# MCU.net
KiCad netlist of a schematic drawn in Altium Designer
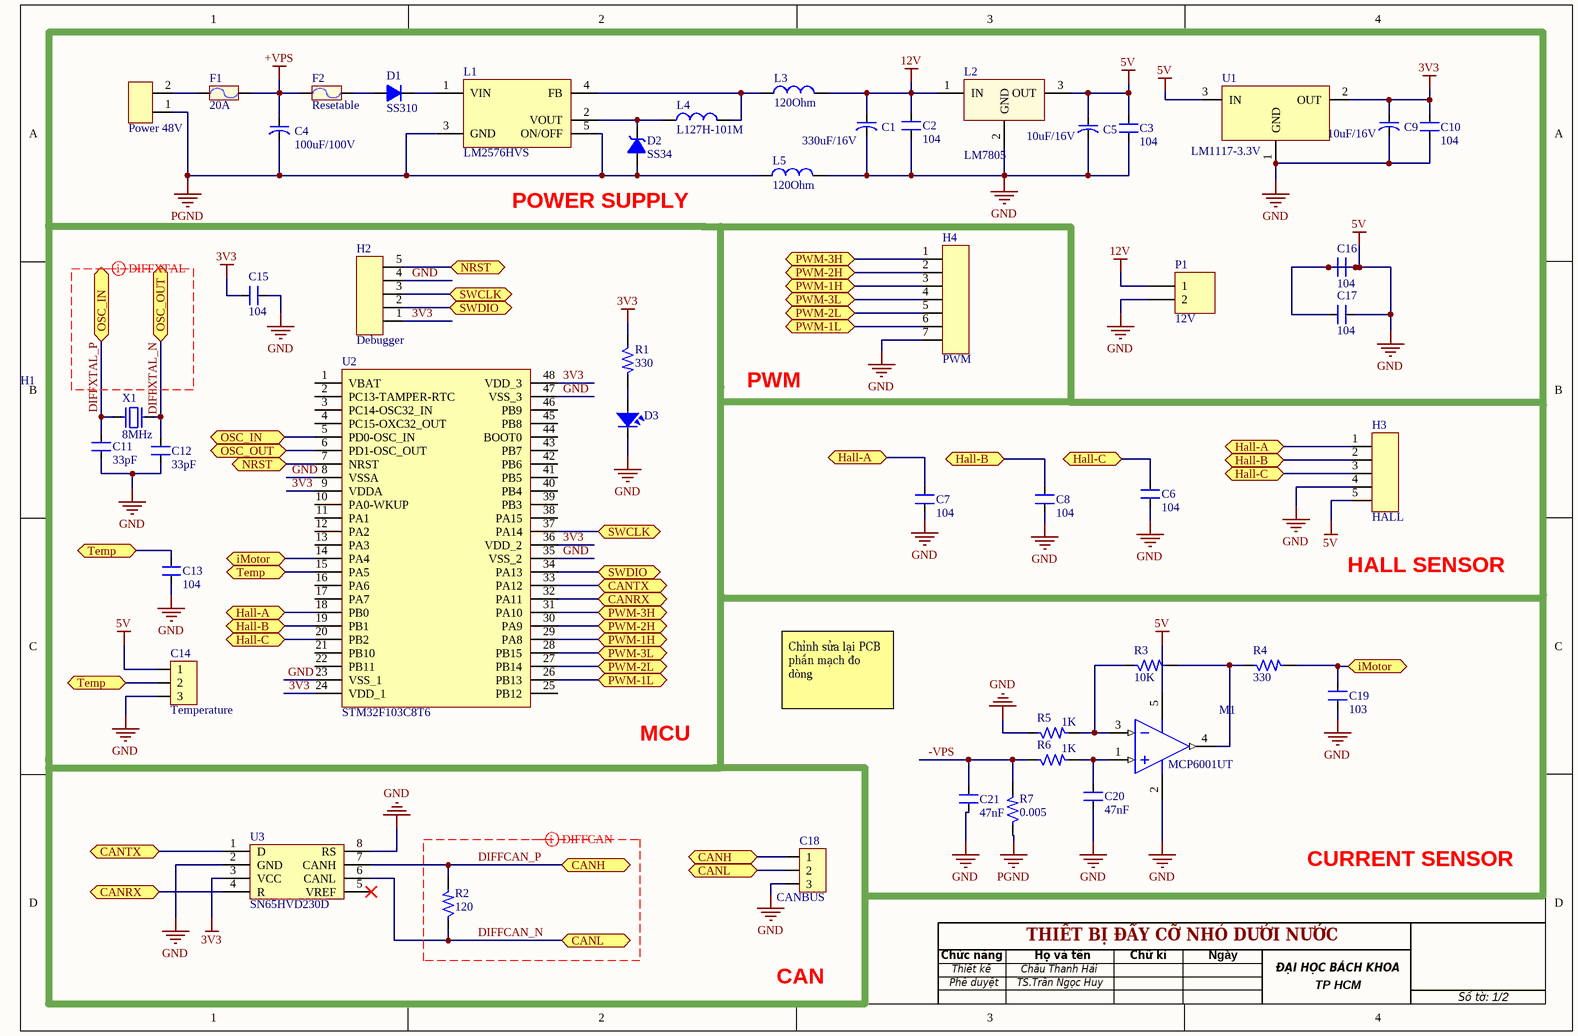
[diagram p0: MCU.SchDoc]

(export (version "E")
  (design (tool "Eeschema 10.0.6"))
  (components
    (comp (ref "C1")
      (value "330uF/16V")
      (footprint "330uF/16V")
      (libsource (lib "BLDC_Libraries") (part "330uF/16V"))
    )
    (comp (ref "C2")
      (value "104")
      (footprint "Non-Capacitor 104 SMD")
      (libsource (lib "BLDC_Libraries") (part "104"))
    )
    (comp (ref "C3")
      (value "104")
      (footprint "Non-Capacitor 104 SMD")
      (libsource (lib "BLDC_Libraries") (part "104"))
    )
    (comp (ref "C4")
      (value "100uF/100V")
      (footprint "100uF/100V")
      (description "DIP Footprint")
      (libsource (lib "BLDC_Libraries") (part "Polary Capacitor"))
    )
    (comp (ref "C5")
      (value "10uF/16V")
      (footprint "10uF/16V")
      (libsource (lib "BLDC_Libraries") (part "10uF/16V"))
    )
    (comp (ref "C6")
      (value "104")
      (footprint "Non-Capacitor 104 SMD")
      (libsource (lib "BLDC_Libraries") (part "104"))
    )
    (comp (ref "C7")
      (value "104")
      (footprint "Non-Capacitor 104 SMD")
      (libsource (lib "BLDC_Libraries") (part "104"))
    )
    (comp (ref "C8")
      (value "104")
      (footprint "Non-Capacitor 104 SMD")
      (libsource (lib "BLDC_Libraries") (part "104"))
    )
    (comp (ref "C9")
      (value "10uF/16V")
      (footprint "10uF/16V")
      (libsource (lib "BLDC_Libraries") (part "10uF/16V"))
    )
    (comp (ref "C10")
      (value "104")
      (footprint "Non-Capacitor 104 SMD")
      (libsource (lib "BLDC_Libraries") (part "104"))
    )
    (comp (ref "C11")
      (value "33pF")
      (footprint "Non-Capacitor 104 SMD")
      (libsource (lib "BLDC_Libraries") (part "104"))
    )
    (comp (ref "C12")
      (value "33pF")
      (footprint "Non-Capacitor 104 SMD")
      (libsource (lib "BLDC_Libraries") (part "104"))
    )
    (comp (ref "C13")
      (value "104")
      (footprint "Non-Capacitor 104 SMD")
      (libsource (lib "BLDC_Libraries") (part "104"))
    )
    (comp (ref "C14")
      (value "Temperature")
      (footprint "Header3")
      (description "Header IDC, 3 x 1 Pin Vertical 2.54mm Pitch (Non-Boxed, Male)")
      (fields
        (field (name "MANUFACTURER") "Würth Elektronik eiSos GmbH")
        (field (name "PARTNO") "613002143121")
        (field (name "CREATED BY") "Karrer Zheng")
      )
      (libsource (lib "LIBRARY") (part "Header3"))
    )
    (comp (ref "C15")
      (value "104")
      (footprint "Non-Capacitor 104 SMD")
      (libsource (lib "BLDC_Libraries") (part "104"))
    )
    (comp (ref "C16")
      (value "104")
      (footprint "Non-Capacitor 104 SMD")
      (libsource (lib "BLDC_Libraries") (part "104"))
    )
    (comp (ref "C17")
      (value "104")
      (footprint "Non-Capacitor 104 SMD")
      (libsource (lib "BLDC_Libraries") (part "104"))
    )
    (comp (ref "C18")
      (value "CANBUS")
      (footprint "Header3")
      (description "Header IDC, 3 x 1 Pin Vertical 2.54mm Pitch (Non-Boxed, Male)")
      (fields
        (field (name "MANUFACTURER") "Würth Elektronik eiSos GmbH")
        (field (name "PARTNO") "613002143121")
        (field (name "CREATED BY") "Karrer Zheng")
      )
      (libsource (lib "LIBRARY") (part "Header3"))
    )
    (comp (ref "C19")
      (value "103")
      (footprint "Non-Capacitor 104 SMD")
      (libsource (lib "BLDC_Libraries") (part "104"))
    )
    (comp (ref "C20")
      (value "47nF")
      (footprint "Non-Capacitor 104 SMD")
      (libsource (lib "BLDC_Libraries") (part "104"))
    )
    (comp (ref "C21")
      (value "47nF")
      (footprint "Non-Capacitor 104 SMD")
      (libsource (lib "BLDC_Libraries") (part "104"))
    )
    (comp (ref "D1") (value "SS310") (footprint "SS310") (libsource (lib "BLDC_Libraries") (part "SS310")))
    (comp (ref "D2") (value "SS34") (footprint "SS34") (libsource (lib "BLDC_Libraries") (part "SS34")))
    (comp (ref "D3")
      (value "LED SMD0603")
      (footprint "Led SMD0603")
      (libsource (lib "BLDC_Libraries") (part "LED SMD0603"))
    )
    (comp (ref "F1") (value "20A") (footprint "Fuse 20A") (libsource (lib "BLDC_Libraries") (part "Fuse")))
    (comp (ref "F2")
      (value "Resetable")
      (footprint "PTC Resettable Fuses")
      (libsource (lib "BLDC_Libraries") (part "Fuse"))
    )
    (comp (ref "H1")
      (value "Power 48V")
      (footprint "Header 2")
      (libsource (lib "BLDC_Libraries") (part "Header 2x1"))
    )
    (comp (ref "H2")
      (value "Debugger")
      (footprint "Header 5")
      (libsource (lib "BLDC_Libraries") (part "Header 5x1"))
    )
    (comp (ref "H3") (value "HALL") (footprint "Header_5_B") (libsource (lib "") (part "Header 5x1_1")))
    (comp (ref "H4")
      (value "PWM")
      (footprint "Header 7 Male")
      (libsource (lib "BLDC_Libraries") (part "Header 7x1"))
    )
    (comp (ref "L1")
      (value "LM2576HVS")
      (footprint "LM2576 SMD")
      (libsource (lib "BLDC_Libraries") (part "LM2576HVS"))
    )
    (comp (ref "L2")
      (value "LM7805")
      (footprint "LM7805 SMD")
      (libsource (lib "BLDC_Libraries") (part "LM7805"))
    )
    (comp (ref "L3")
      (value "120Ohm")
      (footprint "Ferrite Beads")
      (libsource (lib "BLDC_Libraries") (part "Ferrite Beads"))
    )
    (comp (ref "L4")
      (value "L127H-101M")
      (footprint "L127H-101M")
      (libsource (lib "BLDC_Libraries") (part "L127H-101M"))
    )
    (comp (ref "L5")
      (value "120Ohm")
      (footprint "Ferrite Beads")
      (libsource (lib "BLDC_Libraries") (part "Ferrite Beads"))
    )
    (comp (ref "M1")
      (value "MCP6001UT")
      (footprint "MCP6001UT")
      (libsource (lib "BLDC_Libraries") (part "MCP6001UT"))
    )
    (comp (ref "P1")
      (value "12V")
      (footprint "HDR1X2")
      (description "Header, 2-Pin")
      (fields (field (name "PUBLISHER") "Altium Limited"))
      (libsource (lib "NBBLib 14-03-2012") (part "Header 2"))
    )
    (comp (ref "R1")
      (value "330")
      (footprint "Resistor SMD 0603")
      (libsource (lib "BLDC_Libraries") (part "Resistors"))
    )
    (comp (ref "R2")
      (value "120")
      (footprint "Resistor SMD 0603")
      (libsource (lib "BLDC_Libraries") (part "Resistors"))
    )
    (comp (ref "R3")
      (value "10K")
      (footprint "Resistor SMD 0603")
      (libsource (lib "BLDC_Libraries") (part "Resistors"))
    )
    (comp (ref "R4")
      (value "330")
      (footprint "Resistor SMD 0603")
      (libsource (lib "BLDC_Libraries") (part "Resistors"))
    )
    (comp (ref "R5")
      (value "1K")
      (footprint "Resistor SMD 0603")
      (libsource (lib "BLDC_Libraries") (part "Resistors"))
    )
    (comp (ref "R6")
      (value "1K")
      (footprint "Resistor SMD 0603")
      (libsource (lib "BLDC_Libraries") (part "Resistors"))
    )
    (comp (ref "R7")
      (value "0.005")
      (footprint "Shunt")
      (libsource (lib "BLDC_Libraries") (part "Shunt Resistor"))
    )
    (comp (ref "U1")
      (value "LM1117-3.3V")
      (footprint "SOT223")
      (description "800mA Low-Dropout Linear Regulator")
      (fields (field (name "CREATOR") "Nguyen Ba Bien"))
      (libsource (lib "LIBRARY") (part "LM1117"))
    )
    (comp (ref "U2")
      (value "STM32F103C8T6")
      (footprint "STM32F103C8T6")
      (description "ARM® 32-bit Cortex®-M3")
      (libsource (lib "BLDC_Libraries") (part "STM32F103C8T6"))
    )
    (comp (ref "U3")
      (value "SN65HVD230D")
      (footprint "SN65HVD230D")
      (libsource (lib "BLDC_Libraries") (part "SN65HVD230D"))
    )
    (comp (ref "X1") (value "8MHz") (footprint "Crystal") (libsource (lib "BLDC_Libraries") (part "Crystal")))
  )
  (nets
    (net (code "1") (name "+VPS") (class "Default")
      (node (ref "C4") (pin "1") (pinfunction "1_1") (pintype "passive"))
      (node (ref "F1") (pin "2") (pinfunction "2_2") (pintype "passive"))
      (node (ref "F2") (pin "1") (pinfunction "1_1") (pintype "passive"))
    )
    (net (code "2") (name "/-VPS") (class "Default")
      (node (ref "C21") (pin "2") (pinfunction "2_2") (pintype "passive"))
      (node (ref "R6") (pin "1") (pinfunction "1_1") (pintype "passive"))
      (node (ref "R7") (pin "2") (pinfunction "2_2") (pintype "passive"))
    )
    (net (code "3") (name "/CANRX") (class "Default")
      (node (ref "U2") (pin "32") (pinfunction "PA11_32") (pintype "passive"))
      (node (ref "U3") (pin "4") (pinfunction "R_4") (pintype "passive"))
    )
    (net (code "4") (name "/CANTX") (class "Default")
      (node (ref "U2") (pin "33") (pinfunction "PA12_33") (pintype "passive"))
      (node (ref "U3") (pin "1") (pinfunction "D_1") (pintype "passive"))
    )
    (net (code "5") (name "/DIFFCAN_N") (class "Default")
      (node (ref "C18") (pin "2") (pinfunction "2_2") (pintype "passive"))
      (node (ref "R2") (pin "1") (pinfunction "1_1") (pintype "passive"))
      (node (ref "U3") (pin "6") (pinfunction "CANL_6") (pintype "passive"))
    )
    (net (code "6") (name "/DIFFCAN_P") (class "Default")
      (node (ref "C18") (pin "1") (pinfunction "1_1") (pintype "passive"))
      (node (ref "R2") (pin "2") (pinfunction "2_2") (pintype "passive"))
      (node (ref "U3") (pin "7") (pinfunction "CANH_7") (pintype "passive"))
    )
    (net (code "7") (name "/DIFFXTAL_N") (class "Default")
      (node (ref "C12") (pin "2") (pinfunction "2_2") (pintype "passive"))
      (node (ref "U2") (pin "6") (pinfunction "PD1-OSC_OUT_6") (pintype "passive"))
      (node (ref "X1") (pin "2") (pinfunction "2_2") (pintype "passive"))
    )
    (net (code "8") (name "/DIFFXTAL_P") (class "Default")
      (node (ref "C11") (pin "2") (pinfunction "2_2") (pintype "passive"))
      (node (ref "U2") (pin "5") (pinfunction "PD0-OSC_IN_5") (pintype "passive"))
      (node (ref "X1") (pin "1") (pinfunction "1_1") (pintype "passive"))
    )
    (net (code "9") (name "/Hall-A") (class "Default")
      (node (ref "C7") (pin "2") (pinfunction "2_2") (pintype "passive"))
      (node (ref "H3") (pin "1") (pinfunction "1_1") (pintype "passive"))
      (node (ref "U2") (pin "18") (pinfunction "PB0_18") (pintype "passive"))
    )
    (net (code "10") (name "/Hall-B") (class "Default")
      (node (ref "C8") (pin "2") (pinfunction "2_2") (pintype "passive"))
      (node (ref "H3") (pin "2") (pinfunction "2_2") (pintype "passive"))
      (node (ref "U2") (pin "19") (pinfunction "PB1_19") (pintype "passive"))
    )
    (net (code "11") (name "/Hall-C") (class "Default")
      (node (ref "C6") (pin "2") (pinfunction "2_2") (pintype "passive"))
      (node (ref "H3") (pin "3") (pinfunction "3_3") (pintype "passive"))
      (node (ref "U2") (pin "20") (pinfunction "PB2_20") (pintype "passive"))
    )
    (net (code "12") (name "/NRST") (class "Default")
      (node (ref "H2") (pin "5") (pinfunction "5_5") (pintype "passive"))
      (node (ref "U2") (pin "7") (pinfunction "NRST_7") (pintype "passive"))
    )
    (net (code "13") (name "/PWM-1H") (class "Default")
      (node (ref "H4") (pin "3") (pinfunction "3_3") (pintype "passive"))
      (node (ref "U2") (pin "29") (pinfunction "PA8_29") (pintype "passive"))
    )
    (net (code "14") (name "/PWM-1L") (class "Default")
      (node (ref "H4") (pin "6") (pinfunction "6_6") (pintype "passive"))
      (node (ref "U2") (pin "26") (pinfunction "PB13_26") (pintype "passive"))
    )
    (net (code "15") (name "/PWM-2H") (class "Default")
      (node (ref "H4") (pin "2") (pinfunction "2_2") (pintype "passive"))
      (node (ref "U2") (pin "30") (pinfunction "PA9_30") (pintype "passive"))
    )
    (net (code "16") (name "/PWM-2L") (class "Default")
      (node (ref "H4") (pin "5") (pinfunction "5_5") (pintype "passive"))
      (node (ref "U2") (pin "27") (pinfunction "PB14_27") (pintype "passive"))
    )
    (net (code "17") (name "/PWM-3H") (class "Default")
      (node (ref "H4") (pin "1") (pinfunction "1_1") (pintype "passive"))
      (node (ref "U2") (pin "31") (pinfunction "PA10_31") (pintype "passive"))
    )
    (net (code "18") (name "/PWM-3L") (class "Default")
      (node (ref "H4") (pin "4") (pinfunction "4_4") (pintype "passive"))
      (node (ref "U2") (pin "28") (pinfunction "PB15_28") (pintype "passive"))
    )
    (net (code "19") (name "/SWCLK") (class "Default")
      (node (ref "H2") (pin "3") (pinfunction "3_3") (pintype "passive"))
      (node (ref "U2") (pin "37") (pinfunction "PA14_37") (pintype "passive"))
    )
    (net (code "20") (name "/SWDIO") (class "Default")
      (node (ref "H2") (pin "2") (pinfunction "2_2") (pintype "passive"))
      (node (ref "U2") (pin "34") (pinfunction "PA13_34") (pintype "passive"))
    )
    (net (code "21") (name "/Temp") (class "Default")
      (node (ref "C13") (pin "1") (pinfunction "1_1") (pintype "passive"))
      (node (ref "C14") (pin "2") (pinfunction "2_2") (pintype "passive"))
      (node (ref "U2") (pin "15") (pinfunction "PA5_15") (pintype "passive"))
    )
    (net (code "22") (name "/iMotor") (class "Default")
      (node (ref "C19") (pin "2") (pinfunction "2_2") (pintype "passive"))
      (node (ref "R4") (pin "2") (pinfunction "2_2") (pintype "passive"))
      (node (ref "U2") (pin "14") (pinfunction "PA4_14") (pintype "passive"))
    )
    (net (code "23") (name "3V3") (class "Default")
      (node (ref "C10") (pin "2") (pinfunction "2_2") (pintype "passive"))
      (node (ref "C15") (pin "2") (pinfunction "2_2") (pintype "passive"))
      (node (ref "C9") (pin "1") (pinfunction "1_1") (pintype "passive"))
      (node (ref "H2") (pin "1") (pinfunction "1_1") (pintype "passive"))
      (node (ref "R1") (pin "1") (pinfunction "1_1") (pintype "passive"))
      (node (ref "U1") (pin "2") (pinfunction "OUT_2") (pintype "passive"))
      (node (ref "U2") (pin "24") (pinfunction "VDD_1_24") (pintype "passive"))
      (node (ref "U2") (pin "36") (pinfunction "VDD_2_36") (pintype "passive"))
      (node (ref "U2") (pin "48") (pinfunction "VDD_3_48") (pintype "passive"))
      (node (ref "U2") (pin "9") (pinfunction "VDDA_9") (pintype "passive"))
      (node (ref "U3") (pin "3") (pinfunction "VCC_3") (pintype "passive"))
    )
    (net (code "24") (name "5V") (class "Default")
      (node (ref "C1") (pin "2") (pinfunction "2_2") (pintype "passive"))
      (node (ref "C10") (pin "1") (pinfunction "1_1") (pintype "passive"))
      (node (ref "C11") (pin "1") (pinfunction "1_1") (pintype "passive"))
      (node (ref "C12") (pin "1") (pinfunction "1_1") (pintype "passive"))
      (node (ref "C13") (pin "2") (pinfunction "2_2") (pintype "passive"))
      (node (ref "C14") (pin "1") (pinfunction "1_1") (pintype "passive"))
      (node (ref "C14") (pin "3") (pinfunction "3_3") (pintype "passive"))
      (node (ref "C15") (pin "1") (pinfunction "1_1") (pintype "passive"))
      (node (ref "C16") (pin "1") (pinfunction "1_1") (pintype "passive"))
      (node (ref "C16") (pin "2") (pinfunction "2_2") (pintype "passive"))
      (node (ref "C17") (pin "1") (pinfunction "1_1") (pintype "passive"))
      (node (ref "C17") (pin "2") (pinfunction "2_2") (pintype "passive"))
      (node (ref "C18") (pin "3") (pinfunction "3_3") (pintype "passive"))
      (node (ref "C19") (pin "1") (pinfunction "1_1") (pintype "passive"))
      (node (ref "C2") (pin "1") (pinfunction "1_1") (pintype "passive"))
      (node (ref "C20") (pin "1") (pinfunction "1_1") (pintype "passive"))
      (node (ref "C21") (pin "1") (pinfunction "1_1") (pintype "passive"))
      (node (ref "C3") (pin "1") (pinfunction "1_1") (pintype "passive"))
      (node (ref "C3") (pin "2") (pinfunction "2_2") (pintype "passive"))
      (node (ref "C5") (pin "1") (pinfunction "1_1") (pintype "passive"))
      (node (ref "C5") (pin "2") (pinfunction "2_2") (pintype "passive"))
      (node (ref "C6") (pin "1") (pinfunction "1_1") (pintype "passive"))
      (node (ref "C7") (pin "1") (pinfunction "1_1") (pintype "passive"))
      (node (ref "C8") (pin "1") (pinfunction "1_1") (pintype "passive"))
      (node (ref "C9") (pin "2") (pinfunction "2_2") (pintype "passive"))
      (node (ref "D3") (pin "2") (pinfunction "2_2") (pintype "passive"))
      (node (ref "H2") (pin "4") (pinfunction "4_4") (pintype "passive"))
      (node (ref "H3") (pin "4") (pinfunction "4_4") (pintype "passive"))
      (node (ref "H3") (pin "5") (pinfunction "5_5") (pintype "passive"))
      (node (ref "H4") (pin "7") (pinfunction "7_7") (pintype "passive"))
      (node (ref "L2") (pin "2") (pinfunction "GND_2") (pintype "passive"))
      (node (ref "L2") (pin "3") (pinfunction "OUT_3") (pintype "passive"))
      (node (ref "L5") (pin "2") (pinfunction "2_2") (pintype "passive"))
      (node (ref "M1") (pin "2") (pinfunction "V-_2") (pintype "power_in"))
      (node (ref "M1") (pin "5") (pinfunction "V+_5") (pintype "power_in"))
      (node (ref "P1") (pin "2") (pinfunction "2_2") (pintype "passive"))
      (node (ref "R5") (pin "1") (pinfunction "1_1") (pintype "passive"))
      (node (ref "U1") (pin "1") (pinfunction "GND_1") (pintype "passive"))
      (node (ref "U1") (pin "3") (pinfunction "IN_3") (pintype "passive"))
      (node (ref "U2") (pin "23") (pinfunction "VSS_1_23") (pintype "passive"))
      (node (ref "U2") (pin "35") (pinfunction "VSS_2_35") (pintype "passive"))
      (node (ref "U2") (pin "47") (pinfunction "VSS_3_47") (pintype "passive"))
      (node (ref "U2") (pin "8") (pinfunction "VSSA_8") (pintype "passive"))
      (node (ref "U3") (pin "2") (pinfunction "GND_2") (pintype "passive"))
      (node (ref "U3") (pin "8") (pinfunction "RS_8") (pintype "passive"))
    )
    (net (code "25") (name "12V") (class "Default")
      (node (ref "C1") (pin "1") (pinfunction "1_1") (pintype "passive"))
      (node (ref "C2") (pin "2") (pinfunction "2_2") (pintype "passive"))
      (node (ref "L2") (pin "1") (pinfunction "IN_1") (pintype "passive"))
      (node (ref "L3") (pin "2") (pinfunction "2_2") (pintype "passive"))
      (node (ref "P1") (pin "1") (pinfunction "1_1") (pintype "passive"))
    )
    (net (code "26") (name "Net-(D1-A)") (class "Default")
      (node (ref "D1") (pin "2") (pinfunction "A_2") (pintype "passive"))
      (node (ref "F2") (pin "2") (pinfunction "2_2") (pintype "passive"))
    )
    (net (code "27") (name "Net-(D1-K)") (class "Default")
      (node (ref "D1") (pin "1") (pinfunction "K_1") (pintype "passive"))
      (node (ref "L1") (pin "1") (pinfunction "VIN_1") (pintype "passive"))
    )
    (net (code "28") (name "Net-(D2-K)") (class "Default")
      (node (ref "D2") (pin "1") (pinfunction "K_1") (pintype "passive"))
      (node (ref "L1") (pin "2") (pinfunction "VOUT_2") (pintype "passive"))
      (node (ref "L4") (pin "1") (pinfunction "1_1") (pintype "passive"))
    )
    (net (code "29") (name "Net-(D3-Pad1)") (class "Default")
      (node (ref "D3") (pin "1") (pinfunction "1_1") (pintype "passive"))
      (node (ref "R1") (pin "2") (pinfunction "2_2") (pintype "passive"))
    )
    (net (code "30") (name "Net-(F1-Pad1)") (class "Default")
      (node (ref "F1") (pin "1") (pinfunction "1_1") (pintype "passive"))
      (node (ref "H1") (pin "2") (pinfunction "2_2") (pintype "passive"))
    )
    (net (code "31") (name "Net-(L1-FB)") (class "Default")
      (node (ref "L1") (pin "4") (pinfunction "FB_4") (pintype "passive"))
      (node (ref "L3") (pin "1") (pinfunction "1_1") (pintype "passive"))
      (node (ref "L4") (pin "2") (pinfunction "2_2") (pintype "passive"))
    )
    (net (code "32") (name "Net-(M1-IN+)") (class "Default")
      (node (ref "M1") (pin "3") (pinfunction "IN+_3") (pintype "input"))
      (node (ref "R3") (pin "1") (pinfunction "1_1") (pintype "passive"))
      (node (ref "R5") (pin "2") (pinfunction "2_2") (pintype "passive"))
    )
    (net (code "33") (name "Net-(M1-IN-)") (class "Default")
      (node (ref "C20") (pin "2") (pinfunction "2_2") (pintype "passive"))
      (node (ref "M1") (pin "1") (pinfunction "IN-_1") (pintype "input"))
      (node (ref "R6") (pin "2") (pinfunction "2_2") (pintype "passive"))
    )
    (net (code "34") (name "Net-(M1-OUT)") (class "Default")
      (node (ref "M1") (pin "4") (pinfunction "OUT_4") (pintype "output"))
      (node (ref "R3") (pin "2") (pinfunction "2_2") (pintype "passive"))
      (node (ref "R4") (pin "1") (pinfunction "1_1") (pintype "passive"))
    )
    (net (code "35") (name "PGND") (class "Default")
      (node (ref "C4") (pin "2") (pinfunction "2_2") (pintype "passive"))
      (node (ref "D2") (pin "2") (pinfunction "A_2") (pintype "passive"))
      (node (ref "H1") (pin "1") (pinfunction "1_1") (pintype "passive"))
      (node (ref "L1") (pin "3") (pinfunction "GND_3") (pintype "passive"))
      (node (ref "L1") (pin "5") (pinfunction "ON/OFF_5") (pintype "passive"))
      (node (ref "L5") (pin "1") (pinfunction "1_1") (pintype "passive"))
      (node (ref "R7") (pin "1") (pinfunction "1_1") (pintype "passive"))
    )
    (net (code "36") (name "unconnected-(U2-BOOT0-Pad44)") (class "Default")
      (node (ref "U2") (pin "44") (pinfunction "BOOT0_44") (pintype "passive"))
    )
    (net (code "37") (name "unconnected-(U2-PA0-WKUP-Pad10)") (class "Default")
      (node (ref "U2") (pin "10") (pinfunction "PA0-WKUP_10") (pintype "passive"))
    )
    (net (code "38") (name "unconnected-(U2-PA1-Pad11)") (class "Default")
      (node (ref "U2") (pin "11") (pinfunction "PA1_11") (pintype "passive"))
    )
    (net (code "39") (name "unconnected-(U2-PA2-Pad12)") (class "Default")
      (node (ref "U2") (pin "12") (pinfunction "PA2_12") (pintype "passive"))
    )
    (net (code "40") (name "unconnected-(U2-PA3-Pad13)") (class "Default")
      (node (ref "U2") (pin "13") (pinfunction "PA3_13") (pintype "passive"))
    )
    (net (code "41") (name "unconnected-(U2-PA6-Pad16)") (class "Default")
      (node (ref "U2") (pin "16") (pinfunction "PA6_16") (pintype "passive"))
    )
    (net (code "42") (name "unconnected-(U2-PA7-Pad17)") (class "Default")
      (node (ref "U2") (pin "17") (pinfunction "PA7_17") (pintype "passive"))
    )
    (net (code "43") (name "unconnected-(U2-PA15-Pad38)") (class "Default")
      (node (ref "U2") (pin "38") (pinfunction "PA15_38") (pintype "passive"))
    )
    (net (code "44") (name "unconnected-(U2-PB3-Pad39)") (class "Default")
      (node (ref "U2") (pin "39") (pinfunction "PB3_39") (pintype "passive"))
    )
    (net (code "45") (name "unconnected-(U2-PB4-Pad40)") (class "Default")
      (node (ref "U2") (pin "40") (pinfunction "PB4_40") (pintype "passive"))
    )
    (net (code "46") (name "unconnected-(U2-PB5-Pad41)") (class "Default")
      (node (ref "U2") (pin "41") (pinfunction "PB5_41") (pintype "passive"))
    )
    (net (code "47") (name "unconnected-(U2-PB6-Pad42)") (class "Default")
      (node (ref "U2") (pin "42") (pinfunction "PB6_42") (pintype "passive"))
    )
    (net (code "48") (name "unconnected-(U2-PB7-Pad43)") (class "Default")
      (node (ref "U2") (pin "43") (pinfunction "PB7_43") (pintype "passive"))
    )
    (net (code "49") (name "unconnected-(U2-PB8-Pad45)") (class "Default")
      (node (ref "U2") (pin "45") (pinfunction "PB8_45") (pintype "passive"))
    )
    (net (code "50") (name "unconnected-(U2-PB9-Pad46)") (class "Default")
      (node (ref "U2") (pin "46") (pinfunction "PB9_46") (pintype "passive"))
    )
    (net (code "51") (name "unconnected-(U2-PB10-Pad21)") (class "Default")
      (node (ref "U2") (pin "21") (pinfunction "PB10_21") (pintype "passive"))
    )
    (net (code "52") (name "unconnected-(U2-PB11-Pad22)") (class "Default")
      (node (ref "U2") (pin "22") (pinfunction "PB11_22") (pintype "passive"))
    )
    (net (code "53") (name "unconnected-(U2-PB12-Pad25)") (class "Default")
      (node (ref "U2") (pin "25") (pinfunction "PB12_25") (pintype "passive"))
    )
    (net (code "54") (name "unconnected-(U2-PC13-TAMPER-RTC-Pad2)") (class "Default")
      (node (ref "U2") (pin "2") (pinfunction "PC13-TAMPER-RTC_2") (pintype "passive"))
    )
    (net (code "55") (name "unconnected-(U2-PC14-OSC32_IN-Pad3)") (class "Default")
      (node (ref "U2") (pin "3") (pinfunction "PC14-OSC32_IN_3") (pintype "passive"))
    )
    (net (code "56") (name "unconnected-(U2-PC15-OXC32_OUT-Pad4)") (class "Default")
      (node (ref "U2") (pin "4") (pinfunction "PC15-OXC32_OUT_4") (pintype "passive"))
    )
    (net (code "57") (name "unconnected-(U2-VBAT-Pad1)") (class "Default")
      (node (ref "U2") (pin "1") (pinfunction "VBAT_1") (pintype "passive"))
    )
    (net (code "58") (name "unconnected-(U3-VREF-Pad5)") (class "Default")
      (node (ref "U3") (pin "5") (pinfunction "VREF_5") (pintype "passive+no_connect"))
    )
  )
)
